# MCU.net
KiCad netlist of a schematic drawn in Altium Designer
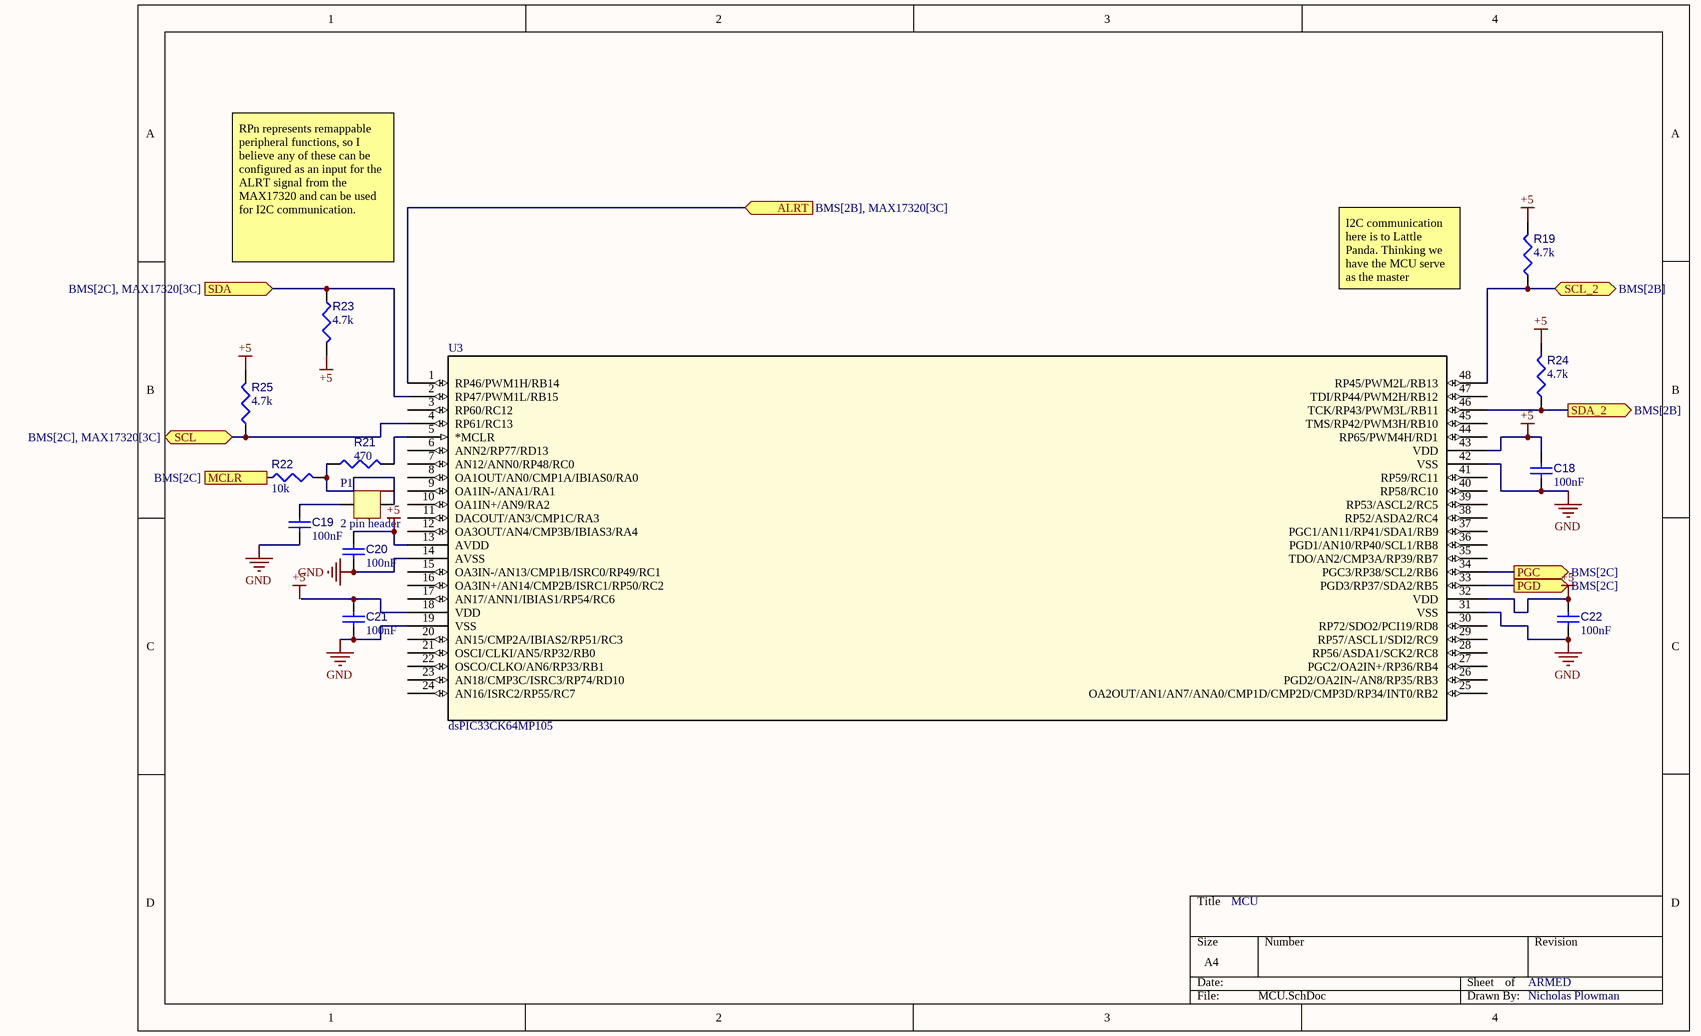
[diagram p0: MCU.SchDoc]

(export (version "E")
  (design (tool "Eeschema 10.0.6"))
  (components
    (comp (ref "C18")
      (value "100nF")
      (footprint "CAPC1005X56X25LL10T15")
      (description "Chip Capacitor, 0.1 uF, +/- 5%, 16 V, 0402 (1005 Metric)")
      (fields (field (name "TOLERANCE") "5%") (field (name "Comment") "Capacitor 0.1 uF +/- 5% 16 V 0402"))
      (libsource (lib "Americas- Augmented Reality for Medicine- University of Calgary") (part "CAP-NP-2"))
    )
    (comp (ref "C19")
      (value "100nF")
      (footprint "CAPC1005X56X25LL10T15")
      (description "Chip Capacitor, 0.1 uF, +/- 5%, 16 V, 0402 (1005 Metric)")
      (fields (field (name "TOLERANCE") "5%") (field (name "Comment") "Capacitor 0.1 uF +/- 5% 16 V 0402"))
      (libsource (lib "Americas- Augmented Reality for Medicine- University of Calgary") (part "CAP-NP-2"))
    )
    (comp (ref "C20")
      (value "100nF")
      (footprint "CAPC1005X56X25LL10T15")
      (description "Chip Capacitor, 0.1 uF, +/- 5%, 16 V, 0402 (1005 Metric)")
      (fields (field (name "TOLERANCE") "5%") (field (name "Comment") "Capacitor 0.1 uF +/- 5% 16 V 0402"))
      (libsource (lib "Americas- Augmented Reality for Medicine- University of Calgary") (part "CAP-NP-2"))
    )
    (comp (ref "C21")
      (value "100nF")
      (footprint "CAPC1005X56X25LL10T15")
      (description "Chip Capacitor, 0.1 uF, +/- 5%, 16 V, 0402 (1005 Metric)")
      (fields (field (name "TOLERANCE") "5%") (field (name "Comment") "Capacitor 0.1 uF +/- 5% 16 V 0402"))
      (libsource (lib "Americas- Augmented Reality for Medicine- University of Calgary") (part "CAP-NP-2"))
    )
    (comp (ref "C22")
      (value "100nF")
      (footprint "CAPC1005X56X25LL10T15")
      (description "Chip Capacitor, 0.1 uF, +/- 5%, 16 V, 0402 (1005 Metric)")
      (fields (field (name "TOLERANCE") "5%") (field (name "Comment") "Capacitor 0.1 uF +/- 5% 16 V 0402"))
      (libsource (lib "Americas- Augmented Reality for Medicine- University of Calgary") (part "CAP-NP-2"))
    )
    (comp (ref "P1")
      (value "2 pin header")
      (footprint "2 pin header-Footprint-1")
      (libsource (lib "Americas- Augmented Reality for Medicine- University of Calgary") (part "2 pin header-Symbol-1"))
    )
    (comp (ref "R19")
      (value "4.7k")
      (footprint "RESC3116X70X50ML13T20")
      (description "Chip Resistor, 4.7 KOhm, +/- 1%, 0.25 W, -55 to 155 degC, 1206 (3216 Metric)")
      (fields (field (name "POWER") "250mW") (field (name "TOLERANCE") "1%"))
      (libsource (lib "Americas- Augmented Reality for Medicine- University of Calgary") (part "RES-2"))
    )
    (comp (ref "R21")
      (value "470")
      (footprint "RESC0805(2012)_L")
      (description "Chip Resistor, 470 Ohms, +/-5%, 125 mW, -55 to 155 degC, 0805")
      (fields (field (name "TOLERANCE") "5%") (field (name "POWER") "125mW"))
      (libsource (lib "Americas- Augmented Reality for Medicine- University of Calgary") (part "RES-2"))
    )
    (comp (ref "R22")
      (value "10k")
      (footprint "RESC3216X60X45ML15T20")
      (description "Chip Resistor, 10 KOhm, +/- 1%, 0.25 W, -55 to 155 degC, 1206 (3216 Metric)")
      (fields (field (name "TOLERANCE") "1%") (field (name "POWER") "250mW"))
      (libsource (lib "Americas- Augmented Reality for Medicine- University of Calgary") (part "RES-2"))
    )
    (comp (ref "R23")
      (value "4.7k")
      (footprint "RESC3116X70X50ML13T20")
      (description "Chip Resistor, 4.7 KOhm, +/- 1%, 0.25 W, -55 to 155 degC, 1206 (3216 Metric)")
      (fields (field (name "POWER") "250mW") (field (name "TOLERANCE") "1%"))
      (libsource (lib "Americas- Augmented Reality for Medicine- University of Calgary") (part "RES-2"))
    )
    (comp (ref "R24")
      (value "4.7k")
      (footprint "RESC3116X70X50ML13T20")
      (description "Chip Resistor, 4.7 KOhm, +/- 1%, 0.25 W, -55 to 155 degC, 1206 (3216 Metric)")
      (fields (field (name "POWER") "250mW") (field (name "TOLERANCE") "1%"))
      (libsource (lib "Americas- Augmented Reality for Medicine- University of Calgary") (part "RES-2"))
    )
    (comp (ref "R25")
      (value "4.7k")
      (footprint "RESC3116X70X50ML13T20")
      (description "Chip Resistor, 4.7 KOhm, +/- 1%, 0.25 W, -55 to 155 degC, 1206 (3216 Metric)")
      (fields (field (name "POWER") "250mW") (field (name "TOLERANCE") "1%"))
      (libsource (lib "Americas- Augmented Reality for Medicine- University of Calgary") (part "RES-2"))
    )
    (comp (ref "U3")
      (value "dsPIC33CK64MP105")
      (footprint "dsPIC33CK64MP105-Footprint-1")
      (description "16-bit MCU/DSC, 64 KB, 8192 Bytes, 100 MHz, 3 to 3.6V, TQFP-48, RoHS")
      (libsource (lib "Americas- Augmented Reality for Medicine- University of Calgary") (part "dsPIC33CK64MP105-Symbol-1"))
    )
  )
  (nets
    (net (code "1") (name "+5") (class "Default")
      (node (ref "C18") (pin "1") (pinfunction "1_1") (pintype "passive"))
      (node (ref "C20") (pin "2") (pinfunction "2_2") (pintype "passive"))
      (node (ref "C22") (pin "1") (pinfunction "1_1") (pintype "passive"))
      (node (ref "R19") (pin "2") (pinfunction "2_2") (pintype "passive"))
      (node (ref "R23") (pin "2") (pinfunction "2_2") (pintype "passive"))
      (node (ref "R24") (pin "2") (pinfunction "2_2") (pintype "passive"))
      (node (ref "R25") (pin "2") (pinfunction "2_2") (pintype "passive"))
      (node (ref "U3") (pin "13") (pinfunction "AVDD_13") (pintype "power_in"))
      (node (ref "U3") (pin "32") (pinfunction "VDD_32") (pintype "power_in"))
      (node (ref "U3") (pin "43") (pinfunction "VDD_43") (pintype "power_in"))
    )
    (net (code "2") (name "/ALRT") (class "Default")
      (node (ref "U3") (pin "1") (pinfunction "RP46/PWM1H/RB14_1") (pintype "bidirectional"))
    )
    (net (code "4") (name "/PGC") (class "Default")
      (node (ref "U3") (pin "34") (pinfunction "PGC3/RP38/SCL2/RB6_34") (pintype "bidirectional"))
    )
    (net (code "5") (name "/PGD") (class "Default")
      (node (ref "U3") (pin "33") (pinfunction "PGD3/RP37/SDA2/RB5_33") (pintype "bidirectional"))
    )
    (net (code "6") (name "/SCL") (class "Default")
      (node (ref "R25") (pin "1") (pinfunction "1_1") (pintype "passive"))
      (node (ref "U3") (pin "4") (pinfunction "RP61/RC13_4") (pintype "bidirectional"))
    )
    (net (code "7") (name "/SCL_2") (class "Default")
      (node (ref "R19") (pin "1") (pinfunction "1_1") (pintype "passive"))
      (node (ref "U3") (pin "48") (pinfunction "RP45/PWM2L/RB13_48") (pintype "bidirectional"))
    )
    (net (code "8") (name "/SDA") (class "Default")
      (node (ref "R23") (pin "1") (pinfunction "1_1") (pintype "passive"))
      (node (ref "U3") (pin "2") (pinfunction "RP47/PWM1L/RB15_2") (pintype "bidirectional"))
    )
    (net (code "9") (name "/SDA_2") (class "Default")
      (node (ref "R24") (pin "1") (pinfunction "1_1") (pintype "passive"))
      (node (ref "U3") (pin "46") (pinfunction "TCK/RP43/PWM3L/RB11_46") (pintype "bidirectional"))
    )
    (net (code "10") (name "GND") (class "Default")
      (node (ref "C18") (pin "2") (pinfunction "2_2") (pintype "passive"))
      (node (ref "C19") (pin "1") (pinfunction "1_1") (pintype "passive"))
      (node (ref "C20") (pin "1") (pinfunction "1_1") (pintype "passive"))
      (node (ref "C21") (pin "1") (pinfunction "1_1") (pintype "passive"))
      (node (ref "C22") (pin "2") (pinfunction "2_2") (pintype "passive"))
      (node (ref "U3") (pin "14") (pinfunction "AVSS_14") (pintype "power_in"))
      (node (ref "U3") (pin "19") (pinfunction "VSS_19") (pintype "power_in"))
      (node (ref "U3") (pin "31") (pinfunction "VSS_31") (pintype "power_in"))
      (node (ref "U3") (pin "42") (pinfunction "VSS_42") (pintype "power_in"))
    )
    (net (code "11") (name "Net-(C19-Pad2)") (class "Default")
      (node (ref "C19") (pin "2") (pinfunction "2_2") (pintype "passive"))
      (node (ref "P1") (pin "1") (pintype "passive"))
    )
    (net (code "12") (name "Net-(C21-Pad2)") (class "Default")
      (node (ref "C21") (pin "2") (pinfunction "2_2") (pintype "passive"))
      (node (ref "U3") (pin "18") (pinfunction "VDD_18") (pintype "power_in"))
    )
    (net (code "13") (name "Net-(P1-Pad2)") (class "Default")
      (node (ref "P1") (pin "2") (pintype "passive"))
      (node (ref "R21") (pin "1") (pinfunction "1_1") (pintype "passive"))
      (node (ref "R22") (pin "2") (pinfunction "2_2") (pintype "passive"))
    )
    (net (code "14") (name "Net-(U3-*MCLR)") (class "Default")
      (node (ref "R21") (pin "2") (pinfunction "2_2") (pintype "passive"))
      (node (ref "U3") (pin "5") (pinfunction "*MCLR_5") (pintype "input"))
    )
    (net (code "15") (name "unconnected-(R22-Pad1)") (class "Default")
      (node (ref "R22") (pin "1") (pinfunction "1_1") (pintype "passive"))
    )
    (net (code "16") (name "unconnected-(U3-AN12{slash}ANN0{slash}RP48{slash}RC0-Pad7)") (class "Default")
      (node (ref "U3") (pin "7") (pinfunction "AN12/ANN0/RP48/RC0_7") (pintype "bidirectional"))
    )
    (net (code "17") (name "unconnected-(U3-AN15{slash}CMP2A{slash}IBIAS2{slash}RP51{slash}RC3-Pad20)") (class "Default")
      (node (ref "U3") (pin "20") (pinfunction "AN15/CMP2A/IBIAS2/RP51/RC3_20") (pintype "bidirectional"))
    )
    (net (code "18") (name "unconnected-(U3-AN16{slash}ISRC2{slash}RP55{slash}RC7-Pad24)") (class "Default")
      (node (ref "U3") (pin "24") (pinfunction "AN16/ISRC2/RP55/RC7_24") (pintype "bidirectional"))
    )
    (net (code "19") (name "unconnected-(U3-AN17{slash}ANN1{slash}IBIAS1{slash}RP54{slash}RC6-Pad17)") (class "Default")
      (node (ref "U3") (pin "17") (pinfunction "AN17/ANN1/IBIAS1/RP54/RC6_17") (pintype "bidirectional"))
    )
    (net (code "20") (name "unconnected-(U3-AN18{slash}CMP3C{slash}ISRC3{slash}RP74{slash}RD10-Pad23)") (class "Default")
      (node (ref "U3") (pin "23") (pinfunction "AN18/CMP3C/ISRC3/RP74/RD10_23") (pintype "bidirectional"))
    )
    (net (code "21") (name "unconnected-(U3-ANN2{slash}RP77{slash}RD13-Pad6)") (class "Default")
      (node (ref "U3") (pin "6") (pinfunction "ANN2/RP77/RD13_6") (pintype "bidirectional"))
    )
    (net (code "22") (name "unconnected-(U3-DACOUT{slash}AN3{slash}CMP1C{slash}RA3-Pad11)") (class "Default")
      (node (ref "U3") (pin "11") (pinfunction "DACOUT/AN3/CMP1C/RA3_11") (pintype "bidirectional"))
    )
    (net (code "23") (name "unconnected-(U3-OA1IN+{slash}AN9{slash}RA2-Pad10)") (class "Default")
      (node (ref "U3") (pin "10") (pinfunction "OA1IN+/AN9/RA2_10") (pintype "bidirectional"))
    )
    (net (code "24") (name "unconnected-(U3-OA1IN-{slash}ANA1{slash}RA1-Pad9)") (class "Default")
      (node (ref "U3") (pin "9") (pinfunction "OA1IN-/ANA1/RA1_9") (pintype "bidirectional"))
    )
    (net (code "25") (name "unconnected-(U3-OA1OUT{slash}AN0{slash}CMP1A{slash}IBIAS0{slash}RA0-Pad8)") (class "Default")
      (node (ref "U3") (pin "8") (pinfunction "OA1OUT/AN0/CMP1A/IBIAS0/RA0_8") (pintype "bidirectional"))
    )
    (net (code "26") (name "unconnected-(U3-OA2OUT{slash}AN1{slash}AN7{slash}ANA0{slash}CMP1D{slash}CMP2D{slash}CMP3D{slash}RP34{slash}INT0{slash}RB2-Pad25)") (class "Default")
      (node (ref "U3") (pin "25") (pinfunction "OA2OUT/AN1/AN7/ANA0/CMP1D/CMP2D/CMP3D/RP34/INT0/RB2_25") (pintype "bidirectional"))
    )
    (net (code "27") (name "unconnected-(U3-OA3IN+{slash}AN14{slash}CMP2B{slash}ISRC1{slash}RP50{slash}RC2-Pad16)") (class "Default")
      (node (ref "U3") (pin "16") (pinfunction "OA3IN+/AN14/CMP2B/ISRC1/RP50/RC2_16") (pintype "bidirectional"))
    )
    (net (code "28") (name "unconnected-(U3-OA3IN-{slash}AN13{slash}CMP1B{slash}ISRC0{slash}RP49{slash}RC1-Pad15)") (class "Default")
      (node (ref "U3") (pin "15") (pinfunction "OA3IN-/AN13/CMP1B/ISRC0/RP49/RC1_15") (pintype "bidirectional"))
    )
    (net (code "29") (name "unconnected-(U3-OA3OUT{slash}AN4{slash}CMP3B{slash}IBIAS3{slash}RA4-Pad12)") (class "Default")
      (node (ref "U3") (pin "12") (pinfunction "OA3OUT/AN4/CMP3B/IBIAS3/RA4_12") (pintype "bidirectional"))
    )
    (net (code "30") (name "unconnected-(U3-OSCI{slash}CLKI{slash}AN5{slash}RP32{slash}RB0-Pad21)") (class "Default")
      (node (ref "U3") (pin "21") (pinfunction "OSCI/CLKI/AN5/RP32/RB0_21") (pintype "bidirectional"))
    )
    (net (code "31") (name "unconnected-(U3-OSCO{slash}CLKO{slash}AN6{slash}RP33{slash}RB1-Pad22)") (class "Default")
      (node (ref "U3") (pin "22") (pinfunction "OSCO/CLKO/AN6/RP33/RB1_22") (pintype "bidirectional"))
    )
    (net (code "32") (name "unconnected-(U3-PGC1{slash}AN11{slash}RP41{slash}SDA1{slash}RB9-Pad37)") (class "Default")
      (node (ref "U3") (pin "37") (pinfunction "PGC1/AN11/RP41/SDA1/RB9_37") (pintype "bidirectional"))
    )
    (net (code "33") (name "unconnected-(U3-PGC2{slash}OA2IN+{slash}RP36{slash}RB4-Pad27)") (class "Default")
      (node (ref "U3") (pin "27") (pinfunction "PGC2/OA2IN+/RP36/RB4_27") (pintype "bidirectional"))
    )
    (net (code "34") (name "unconnected-(U3-PGD1{slash}AN10{slash}RP40{slash}SCL1{slash}RB8-Pad36)") (class "Default")
      (node (ref "U3") (pin "36") (pinfunction "PGD1/AN10/RP40/SCL1/RB8_36") (pintype "bidirectional"))
    )
    (net (code "35") (name "unconnected-(U3-PGD2{slash}OA2IN-{slash}AN8{slash}RP35{slash}RB3-Pad26)") (class "Default")
      (node (ref "U3") (pin "26") (pinfunction "PGD2/OA2IN-/AN8/RP35/RB3_26") (pintype "bidirectional"))
    )
    (net (code "36") (name "unconnected-(U3-RP52{slash}ASDA2{slash}RC4-Pad38)") (class "Default")
      (node (ref "U3") (pin "38") (pinfunction "RP52/ASDA2/RC4_38") (pintype "bidirectional"))
    )
    (net (code "37") (name "unconnected-(U3-RP53{slash}ASCL2{slash}RC5-Pad39)") (class "Default")
      (node (ref "U3") (pin "39") (pinfunction "RP53/ASCL2/RC5_39") (pintype "bidirectional"))
    )
    (net (code "38") (name "unconnected-(U3-RP56{slash}ASDA1{slash}SCK2{slash}RC8-Pad28)") (class "Default")
      (node (ref "U3") (pin "28") (pinfunction "RP56/ASDA1/SCK2/RC8_28") (pintype "bidirectional"))
    )
    (net (code "39") (name "unconnected-(U3-RP57{slash}ASCL1{slash}SDI2{slash}RC9-Pad29)") (class "Default")
      (node (ref "U3") (pin "29") (pinfunction "RP57/ASCL1/SDI2/RC9_29") (pintype "bidirectional"))
    )
    (net (code "40") (name "unconnected-(U3-RP58{slash}RC10-Pad40)") (class "Default")
      (node (ref "U3") (pin "40") (pinfunction "RP58/RC10_40") (pintype "bidirectional"))
    )
    (net (code "41") (name "unconnected-(U3-RP59{slash}RC11-Pad41)") (class "Default")
      (node (ref "U3") (pin "41") (pinfunction "RP59/RC11_41") (pintype "bidirectional"))
    )
    (net (code "42") (name "unconnected-(U3-RP60{slash}RC12-Pad3)") (class "Default")
      (node (ref "U3") (pin "3") (pinfunction "RP60/RC12_3") (pintype "bidirectional"))
    )
    (net (code "43") (name "unconnected-(U3-RP65{slash}PWM4H{slash}RD1-Pad44)") (class "Default")
      (node (ref "U3") (pin "44") (pinfunction "RP65/PWM4H/RD1_44") (pintype "bidirectional"))
    )
    (net (code "44") (name "unconnected-(U3-RP72{slash}SDO2{slash}PCI19{slash}RD8-Pad30)") (class "Default")
      (node (ref "U3") (pin "30") (pinfunction "RP72/SDO2/PCI19/RD8_30") (pintype "bidirectional"))
    )
    (net (code "45") (name "unconnected-(U3-TDI{slash}RP44{slash}PWM2H{slash}RB12-Pad47)") (class "Default")
      (node (ref "U3") (pin "47") (pinfunction "TDI/RP44/PWM2H/RB12_47") (pintype "bidirectional"))
    )
    (net (code "46") (name "unconnected-(U3-TDO{slash}AN2{slash}CMP3A{slash}RP39{slash}RB7-Pad35)") (class "Default")
      (node (ref "U3") (pin "35") (pinfunction "TDO/AN2/CMP3A/RP39/RB7_35") (pintype "bidirectional"))
    )
    (net (code "47") (name "unconnected-(U3-TMS{slash}RP42{slash}PWM3H{slash}RB10-Pad45)") (class "Default")
      (node (ref "U3") (pin "45") (pinfunction "TMS/RP42/PWM3H/RB10_45") (pintype "bidirectional"))
    )
  )
)
